# Patil_Sheet_1_20181208.net
KiCad netlist of a schematic drawn in Altium Designer
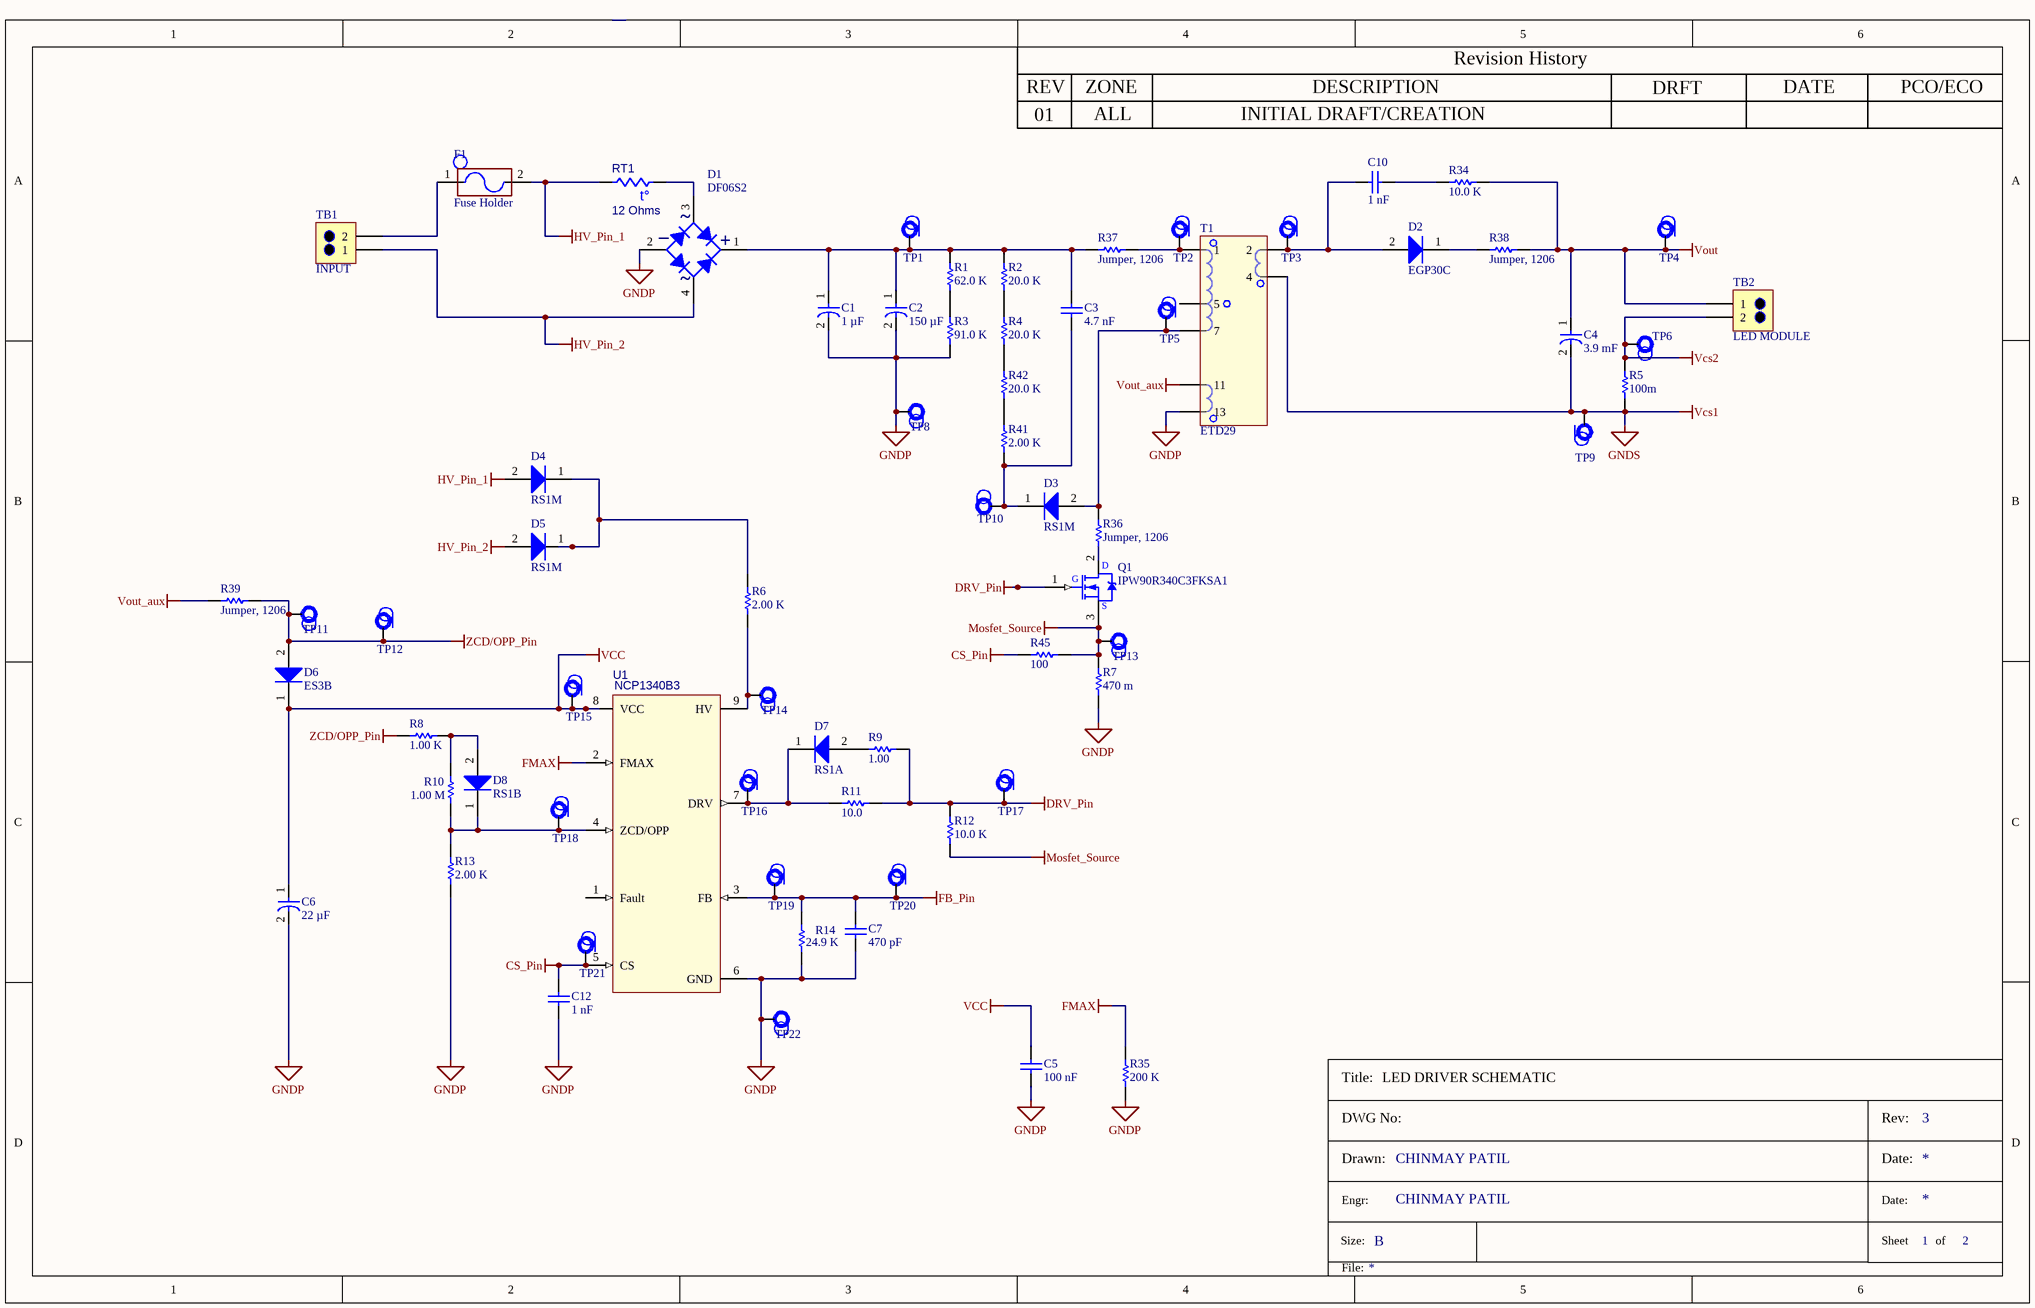
[diagram p0: Patil_Sheet_1_20181208.SchDoc]

(export (version "E")
  (design (tool "Eeschema 10.0.6"))
  (components
    (comp (ref "C1")
      (value "1 µF")
      (footprint "CAP-RAD-THRU-L17.5 X W7.8 X LS15.0 X H11.0MM")
      (description "Capacitor, Film, 1 µF, ±5%, 450 V, Metallized Polypropylene, Radial, Lead")
      (fields (field (name "DISTRIBUTOR PART NUMBER") "PCF1616-ND") (field (name "MANUFACTURER") "Panasonic"))
      (libsource (lib "CU_Boulder_ECEN5009_16-Capacitors") (part "16-0009-002"))
    )
    (comp (ref "C2")
      (value "150 µF")
      (footprint "CAP-SNAP_D25 X H35MM_A35")
      (description "Capacitor, Al. El., 150 µF, ±20%, 450 V, Radial, Snap")
      (fields
        (field (name "DISTRIBUTOR PART NUMBER") "493-17561-ND")
        (field (name "MANUFACTURER") "Nichicon")
      )
      (libsource (lib "CU_Boulder_ECEN5009_16-Capacitors") (part "16-0003-003"))
    )
    (comp (ref "C3")
      (value "4.7 nF")
      (footprint "CAP-1210M_IPC")
      (description "Capacitor, Ceramic, 4.7 nF, ±10%, 1000 V, X7R, 1210")
      (fields (field (name "TOLERANCE") "±10%") (field (name "MANUFACTURER") "Vishay Vitramon"))
      (libsource (lib "CU_Boulder_ECEN5009_16-Capacitors") (part "16-0010-003"))
    )
    (comp (ref "C4")
      (value "3.9 mF")
      (footprint "CAP-RAD-THRU-D18.0 X LS7.5 X H40.0MM")
      (description "Capacitor, Al. El., 3.9 mF, ±20%, 35 V, Radial, Lead")
      (fields (field (name "DISTRIBUTOR PART NUMBER") "493-1602-ND") (field (name "MANUFACTURER") "Nichicon"))
      (libsource (lib "CU_Boulder_ECEN5009_16-Capacitors") (part "16-0006-007"))
    )
    (comp (ref "C5")
      (value "100 nF")
      (footprint "CAP-0805M_IPC")
      (description "Capacitor, Ceramic, 100 nF, ±10%, 50 V, X7R, 0805")
      (fields (field (name "TOLERANCE") "±10%") (field (name "MANUFACTURER") "TDK"))
      (libsource (lib "CU_Boulder_ECEN5009_16-Capacitors") (part "16-0001-066"))
    )
    (comp (ref "C6")
      (value "22 µF")
      (footprint "CAPAE660X540M_CASE-D_IPC")
      (description "Capacitor, Al. El., 22 µF, ±20%, 35 V, SMT")
      (fields
        (field (name "DISTRIBUTOR PART NUMBER") "PCE4025CT-ND")
        (field (name "MANUFACTURER") "Panasonic")
      )
      (libsource (lib "CU_Boulder_ECEN5009_16-Capacitors") (part "16-0005-007"))
    )
    (comp (ref "C7")
      (value "470 pF")
      (footprint "CAP-0805M_IPC")
      (description "Capacitor, Ceramic, 470 pF, ±5%, 50 V, NP0, 0805")
      (fields (field (name "TOLERANCE") "±5%") (field (name "MANUFACTURER") "TDK"))
      (libsource (lib "CU_Boulder_ECEN5009_16-Capacitors") (part "16-0001-038"))
    )
    (comp (ref "C10")
      (value "1 nF")
      (footprint "CAP-1210M_IPC")
      (description "Capacitor, Ceramic, 1 nF, ±10%, 1000 V, X7R, 1210")
      (fields (field (name "TOLERANCE") "±10%") (field (name "MANUFACTURER") "Vishay Vitramon"))
      (libsource (lib "CU_Boulder_ECEN5009_16-Capacitors") (part "16-0010-001"))
    )
    (comp (ref "C12")
      (value "1 nF")
      (footprint "CAP-0805M_IPC")
      (description "Capacitor, Ceramic, 1 nF, ±5%, 50 V, NP0, 0805")
      (fields (field (name "TOLERANCE") "±5%") (field (name "MANUFACTURER") "TDK"))
      (libsource (lib "CU_Boulder_ECEN5009_16-Capacitors") (part "16-0001-042"))
    )
    (comp (ref "D1")
      (value "DF06S2")
      (footprint "SOIC510P1040X260-4M_IPC")
      (description "Diode, Bridge, Std Recovery, DF06S2, 600 V, 2 A, SDIP-4")
      (fields (field (name "DISTRIBUTOR PART NUMBER") "DF06S2CT-ND") (field (name "MANUFACTURER") "ON Semi"))
      (libsource (lib "CU_Boulder_ECEN5009_13-Diodes") (part "13-0015-001"))
    )
    (comp (ref "D2")
      (value "EGP30C")
      (footprint "DIO-AXIAL-DO-201AD")
      (description "Diode, Fast Recovery, EGP30C, 150 V, 3 A, DO-201AD")
      (fields (field (name "DISTRIBUTOR PART NUMBER") "EGP30CCT-ND") (field (name "MANUFACTURER") "ON Semi"))
      (libsource (lib "CU_Boulder_ECEN5009_13-Diodes") (part "13-0023-001"))
    )
    (comp (ref "D3")
      (value "RS1M")
      (footprint "DIODE-SMA-DO214AC")
      (description "Diode, Fast Recovery, RS1M, 1000 V, 1 A, SMA")
      (fields (field (name "DISTRIBUTOR PART NUMBER") "RS1MFSCT-ND") (field (name "MANUFACTURER") "ON Semi"))
      (libsource (lib "CU_Boulder_ECEN5009_13-Diodes") (part "13-0001-007"))
    )
    (comp (ref "D4")
      (value "RS1M")
      (footprint "DIODE-SMA-DO214AC")
      (description "Diode, Fast Recovery, RS1M, 1000 V, 1 A, SMA")
      (fields (field (name "DISTRIBUTOR PART NUMBER") "RS1MFSCT-ND") (field (name "MANUFACTURER") "ON Semi"))
      (libsource (lib "CU_Boulder_ECEN5009_13-Diodes") (part "13-0001-007"))
    )
    (comp (ref "D5")
      (value "RS1M")
      (footprint "DIODE-SMA-DO214AC")
      (description "Diode, Fast Recovery, RS1M, 1000 V, 1 A, SMA")
      (fields (field (name "DISTRIBUTOR PART NUMBER") "RS1MFSCT-ND") (field (name "MANUFACTURER") "ON Semi"))
      (libsource (lib "CU_Boulder_ECEN5009_13-Diodes") (part "13-0001-007"))
    )
    (comp (ref "D6")
      (value "ES3B")
      (footprint "DIODE-SMC-DO214AB")
      (description "Diode, Fast Recovery, ES3B, 100 V, 3 A, SMC")
      (fields
        (field (name "DISTRIBUTOR PART NUMBER") "ES3BFSCT-ND")
        (field (name "MANUFACTURER") "ON Semiconductor")
      )
      (libsource (lib "CU_Boulder_ECEN5009_13-Diodes") (part "13-0026-002"))
    )
    (comp (ref "D7")
      (value "RS1A")
      (footprint "DIODE-SMA-DO214AC")
      (description "Diode, Fast Recovery, RS1A, 50 V, 1 A, SMA")
      (fields (field (name "DISTRIBUTOR PART NUMBER") "RS1ACT-ND") (field (name "MANUFACTURER") "ON Semi"))
      (libsource (lib "CU_Boulder_ECEN5009_13-Diodes") (part "13-0001-001"))
    )
    (comp (ref "D8")
      (value "RS1B")
      (footprint "DIODE-SMA-DO214AC")
      (description "Diode, Fast Recovery, RS1B, 100 V, 1 A, SMA")
      (fields (field (name "DISTRIBUTOR PART NUMBER") "RS1BFSCT-ND") (field (name "MANUFACTURER") "ON Semi"))
      (libsource (lib "CU_Boulder_ECEN5009_13-Diodes") (part "13-0001-002"))
    )
    (comp (ref "F1")
      (value "Fuse Holder")
      (footprint "FUSE_HOLDER_3AG_4527")
      (description "Fuse Holder, TH, 5mm, 3AG")
      (fields
        (field (name "MANUFACTURER") "Keystone Electronics")
        (field (name "MANUFACTURER PART NUMBER") "4527")
      )
      (libsource (lib "CU_Boulder_ECEN5009_18-Electromechanical") (part "18-0012-001"))
    )
    (comp (ref "Q1")
      (value "IPW90R340C3FKSA1")
      (footprint "TO546P508X1588X2483-3A_IPC")
      (description "MOSFET, N-Channel, IPW90R340C3FKSA1, 900 V, 340 mOhm, TO-247")
      (fields
        (field (name "DISTRIBUTOR PART NUMBER") "IPW90R340C3FKSA1-ND")
        (field (name "MANUFACTURER") "Infineon")
      )
      (libsource (lib "CU_Boulder_ECEN5009_10-Transistors") (part "10-0016-002"))
    )
    (comp (ref "R1")
      (value "62.0 K")
      (footprint "RES-AXIAL-2W_IPC")
      (description "Resistor, TH, 62.0 K, 5%, 2 W, MO, Axial")
      (fields (field (name "DISTRIBUTOR PART NUMBER") "62KW-2-ND") (field (name "MANUFACTURER") "Yageo"))
      (libsource (lib "CU_Boulder_ECEN5009_15-Resistors") (part "15-0005-124"))
    )
    (comp (ref "R2")
      (value "20.0 K")
      (footprint "RES-2512M_IPC")
      (description "Resistor, SMT, 20.0 K, 5%, 1 W, 2512")
      (fields (field (name "DISTRIBUTOR PART NUMBER") "15-0004-129") (field (name "TOLERANCE") "5%"))
      (libsource (lib "CU_Boulder_ECEN5009_15-Resistors") (part "15-0004-129"))
    )
    (comp (ref "R3")
      (value "91.0 K")
      (footprint "RES-AXIAL-2W_IPC")
      (description "Resistor, TH, 91.0 K, 5%, 2 W, MO, Axial")
      (fields (field (name "DISTRIBUTOR PART NUMBER") "91KW-2-ND") (field (name "MANUFACTURER") "Yageo"))
      (libsource (lib "CU_Boulder_ECEN5009_15-Resistors") (part "15-0005-128"))
    )
    (comp (ref "R4")
      (value "20.0 K")
      (footprint "RES-2512M_IPC")
      (description "Resistor, SMT, 20.0 K, 5%, 1 W, 2512")
      (fields (field (name "DISTRIBUTOR PART NUMBER") "15-0004-129") (field (name "TOLERANCE") "5%"))
      (libsource (lib "CU_Boulder_ECEN5009_15-Resistors") (part "15-0004-129"))
    )
    (comp (ref "R5")
      (value "100m")
      (footprint "RES-2512M_IPC")
      (description "Resistor, SMT, 100m, 1%, 1 W, 2512")
      (fields (field (name "DISTRIBUTOR PART NUMBER") "311-0.1TCT-ND") (field (name "MANUFACTURER") "Yageo"))
      (libsource (lib "CU_Boulder_ECEN5009_15-Resistors") (part "15-0012-001"))
    )
    (comp (ref "R6")
      (value "2.00 K")
      (footprint "RES-AXIAL-2W_IPC")
      (description "Resistor, TH, 2.00 K, 5%, 2 W, MO, Axial")
      (fields (field (name "DISTRIBUTOR PART NUMBER") "2.0KW-2-ND") (field (name "MANUFACTURER") "Yageo"))
      (libsource (lib "CU_Boulder_ECEN5009_15-Resistors") (part "15-0005-088"))
    )
    (comp (ref "R7")
      (value "470 m")
      (footprint "RES-2512M_IPC")
      (description "Resistor, SMT, 470 m, 1%, 1 W, 2512")
      (fields (field (name "DISTRIBUTOR PART NUMBER") "311-0.47TCT-ND") (field (name "MANUFACTURER") "Yageo"))
      (libsource (lib "CU_Boulder_ECEN5009_15-Resistors") (part "15-0012-003"))
    )
    (comp (ref "R8")
      (value "1.00 K")
      (footprint "RES-2512M_IPC")
      (description "Resistor, SMT, 1.00 K, 5%, 1 W, 2512")
      (fields (field (name "DISTRIBUTOR PART NUMBER") "15-0004-098") (field (name "TOLERANCE") "5%"))
      (libsource (lib "CU_Boulder_ECEN5009_15-Resistors") (part "15-0004-098"))
    )
    (comp (ref "R9")
      (value "1.00")
      (footprint "RES-0805M_IPC")
      (description "Resistor, SMT, 1.00, 1%, 125 mW, 0805")
      (fields (field (name "TOLERANCE") "1%") (field (name "MANUFACTURER") "Yageo"))
      (libsource (lib "CU_Boulder_ECEN5009_15-Resistors") (part "15-0002-001"))
    )
    (comp (ref "R10")
      (value "1.00 M")
      (footprint "RES-1206M_IPC")
      (description "Resistor, SMT, 1.00 M, 1%, 250 mW, 1206")
      (fields (field (name "DISTRIBUTOR PART NUMBER") "15-0003-577") (field (name "MANUFACTURER") "Yageo"))
      (libsource (lib "CU_Boulder_ECEN5009_15-Resistors") (part "15-0003-577"))
    )
    (comp (ref "R11")
      (value "10.0")
      (footprint "RES-0805M_IPC")
      (description "Resistor, SMT, 10.0, 1%, 125 mW, 0805")
      (fields (field (name "DISTRIBUTOR PART NUMBER") "15-0002-097") (field (name "MANUFACTURER") "Yageo"))
      (libsource (lib "CU_Boulder_ECEN5009_15-Resistors") (part "15-0002-097"))
    )
    (comp (ref "R12")
      (value "10.0 K")
      (footprint "RES-1206M_IPC")
      (description "Resistor, SMT, 10.0 K, 1%, 250 mW, 1206")
      (fields (field (name "DISTRIBUTOR PART NUMBER") "15-0003-385") (field (name "MANUFACTURER") "Yageo"))
      (libsource (lib "CU_Boulder_ECEN5009_15-Resistors") (part "15-0003-385"))
    )
    (comp (ref "R13")
      (value "2.00 K")
      (footprint "RES-2512M_IPC")
      (description "Resistor, SMT, 2.00 K, 5%, 1 W, 2512")
      (fields (field (name "DISTRIBUTOR PART NUMBER") "15-0004-105") (field (name "TOLERANCE") "5%"))
      (libsource (lib "CU_Boulder_ECEN5009_15-Resistors") (part "15-0004-105"))
    )
    (comp (ref "R14")
      (value "24.9 K")
      (footprint "RES-1206M_IPC")
      (description "Resistor, SMT, 24.9 K, 1%, 250 mW, 1206")
      (fields (field (name "DISTRIBUTOR PART NUMBER") "15-0003-423") (field (name "MANUFACTURER") "Yageo"))
      (libsource (lib "CU_Boulder_ECEN5009_15-Resistors") (part "15-0003-423"))
    )
    (comp (ref "R34")
      (value "10.0 K")
      (footprint "RES-2512M_IPC")
      (description "Resistor, SMT, 10.0 K, 5%, 1 W, 2512")
      (fields (field (name "DISTRIBUTOR PART NUMBER") "15-0004-122") (field (name "TOLERANCE") "5%"))
      (libsource (lib "CU_Boulder_ECEN5009_15-Resistors") (part "15-0004-122"))
    )
    (comp (ref "R35")
      (value "200 K")
      (footprint "RES-1206M_IPC")
      (description "Resistor, SMT, 200 K, 1%, 250 mW, 1206")
      (fields (field (name "DISTRIBUTOR PART NUMBER") "15-0003-510") (field (name "MANUFACTURER") "Yageo"))
      (libsource (lib "CU_Boulder_ECEN5009_15-Resistors") (part "15-0003-510"))
    )
    (comp (ref "R36")
      (value "Jumper, 1206")
      (footprint "RES-1206M_IPC")
      (libsource (lib "CU_Boulder_ECEN5009_15-Resistors") (part "15-0001-002"))
    )
    (comp (ref "R37")
      (value "Jumper, 1206")
      (footprint "RES-1206M_IPC")
      (libsource (lib "CU_Boulder_ECEN5009_15-Resistors") (part "15-0001-002"))
    )
    (comp (ref "R38")
      (value "Jumper, 1206")
      (footprint "RES-1206M_IPC")
      (libsource (lib "CU_Boulder_ECEN5009_15-Resistors") (part "15-0001-002"))
    )
    (comp (ref "R39")
      (value "Jumper, 1206")
      (footprint "RES-1206M_IPC")
      (libsource (lib "CU_Boulder_ECEN5009_15-Resistors") (part "15-0001-002"))
    )
    (comp (ref "R41")
      (value "2.00 K")
      (footprint "RES-2512M_IPC")
      (description "Resistor, SMT, 2.00 K, 5%, 1 W, 2512")
      (fields (field (name "DISTRIBUTOR PART NUMBER") "15-0004-105") (field (name "TOLERANCE") "5%"))
      (libsource (lib "CU_Boulder_ECEN5009_15-Resistors") (part "15-0004-105"))
    )
    (comp (ref "R42")
      (value "20.0 K")
      (footprint "RES-2512M_IPC")
      (description "Resistor, SMT, 20.0 K, 5%, 1 W, 2512")
      (fields (field (name "DISTRIBUTOR PART NUMBER") "15-0004-129") (field (name "TOLERANCE") "5%"))
      (libsource (lib "CU_Boulder_ECEN5009_15-Resistors") (part "15-0004-129"))
    )
    (comp (ref "R45")
      (value "100")
      (footprint "RES-0805M_IPC")
      (description "Resistor, SMT, 100, 1%, 125 mW, 0805")
      (fields (field (name "DISTRIBUTOR PART NUMBER") "15-0002-193") (field (name "MANUFACTURER") "Yageo"))
      (libsource (lib "CU_Boulder_ECEN5009_15-Resistors") (part "15-0002-193"))
    )
    (comp (ref "RT1")
      (value "12 Ohms")
      (footprint "THERM-RADIAL-15.5MM_DIA_X6MM_THK")
      (description "Inrush Limiter, 12 Ohms, ±20%, 3 A, 15.5 mm, Radial")
      (fields (field (name "DISTRIBUTOR PART NUMBER") "317-1200-ND") (field (name "MANUFACTURER") "Cantherm"))
      (libsource (lib "CU_Boulder_ECEN5009_15-Resistors") (part "15-0010-003"))
    )
    (comp (ref "T1")
      (value "ETD29")
      (footprint "TRANS508P3530X3520X2500-13A_IPC")
      (description "Bobbin, ETD29, Horzontal, 13 Pins")
      (fields
        (field (name "DISTRIBUTOR PART NUMBER") "495-5455-ND")
        (field (name "MANUFACTURER") "TDK/EPCOS")
      )
      (libsource (lib "CU_Boulder_ECEN5009_17-Magnetics") (part "17-0002-002"))
    )
    (comp (ref "TB1")
      (value "INPUT")
      (footprint "CONN_2-POS_TERMINAL_BLOCK_1729128")
      (description "Terminal Block, 2 Pos., Vertical, 14-30 AWG, 5.08 mm")
      (fields
        (field (name "MANUFACTURER") "Phoenix Contact")
        (field (name "MANUFACTURER PART NUMBER") "1729128")
      )
      (libsource (lib "") (part "18-0008-001_1"))
    )
    (comp (ref "TB2")
      (value "LED MODULE")
      (footprint "CONN_2-POS_TERMINAL_BLOCK_1729128")
      (description "Terminal Block, 2 Pos., Vertical, 14-30 AWG, 5.08 mm")
      (fields
        (field (name "MANUFACTURER") "Phoenix Contact")
        (field (name "MANUFACTURER PART NUMBER") "1729128")
      )
      (libsource (lib "CU_Boulder_ECEN5009_18-Electromechanical") (part "18-0008-001"))
    )
    (comp (ref "TP1")
      (value "Test Point")
      (footprint "TP_SMT_LOOP-5019_3D")
      (description "Test Point, SMT, Miniature")
      (fields
        (field (name "MANUFACTURER") "Keystone Electronics")
        (field (name "MANUFACTURER PART NUMBER") "5019")
      )
      (libsource (lib "CU_Boulder_ECEN5009_18-Electromechanical") (part "18-0011-002"))
    )
    (comp (ref "TP2")
      (value "Test Point")
      (footprint "TP_SMT_LOOP-5019_3D")
      (description "Test Point, SMT, Miniature")
      (fields
        (field (name "MANUFACTURER") "Keystone Electronics")
        (field (name "MANUFACTURER PART NUMBER") "5019")
      )
      (libsource (lib "CU_Boulder_ECEN5009_18-Electromechanical") (part "18-0011-002"))
    )
    (comp (ref "TP3")
      (value "Test Point")
      (footprint "TP_SMT_LOOP-5019_3D")
      (description "Test Point, SMT, Miniature")
      (fields
        (field (name "MANUFACTURER") "Keystone Electronics")
        (field (name "MANUFACTURER PART NUMBER") "5019")
      )
      (libsource (lib "CU_Boulder_ECEN5009_18-Electromechanical") (part "18-0011-002"))
    )
    (comp (ref "TP4")
      (value "Test Point")
      (footprint "TP_SMT_LOOP-5019_3D")
      (description "Test Point, SMT, Miniature")
      (fields
        (field (name "MANUFACTURER") "Keystone Electronics")
        (field (name "MANUFACTURER PART NUMBER") "5019")
      )
      (libsource (lib "CU_Boulder_ECEN5009_18-Electromechanical") (part "18-0011-002"))
    )
    (comp (ref "TP5")
      (value "Test Point")
      (footprint "TP_SMT_LOOP-5019_3D")
      (description "Test Point, SMT, Miniature")
      (fields
        (field (name "MANUFACTURER") "Keystone Electronics")
        (field (name "MANUFACTURER PART NUMBER") "5019")
      )
      (libsource (lib "CU_Boulder_ECEN5009_18-Electromechanical") (part "18-0011-002"))
    )
    (comp (ref "TP6")
      (value "Test Point")
      (footprint "TP_SMT_LOOP-5019_3D")
      (description "Test Point, SMT, Miniature")
      (fields
        (field (name "MANUFACTURER") "Keystone Electronics")
        (field (name "MANUFACTURER PART NUMBER") "5019")
      )
      (libsource (lib "CU_Boulder_ECEN5009_18-Electromechanical") (part "18-0011-002"))
    )
    (comp (ref "TP8")
      (value "Test Point")
      (footprint "TP_SMT_LOOP-5019_3D")
      (description "Test Point, SMT, Miniature")
      (fields
        (field (name "MANUFACTURER") "Keystone Electronics")
        (field (name "MANUFACTURER PART NUMBER") "5019")
      )
      (libsource (lib "CU_Boulder_ECEN5009_18-Electromechanical") (part "18-0011-002"))
    )
    (comp (ref "TP9")
      (value "Test Point")
      (footprint "TP_SMT_LOOP-5019_3D")
      (description "Test Point, SMT, Miniature")
      (fields
        (field (name "MANUFACTURER") "Keystone Electronics")
        (field (name "MANUFACTURER PART NUMBER") "5019")
      )
      (libsource (lib "CU_Boulder_ECEN5009_18-Electromechanical") (part "18-0011-002"))
    )
    (comp (ref "TP10")
      (value "Test Point")
      (footprint "TP_SMT_LOOP-5019_3D")
      (description "Test Point, SMT, Miniature")
      (fields
        (field (name "MANUFACTURER") "Keystone Electronics")
        (field (name "MANUFACTURER PART NUMBER") "5019")
      )
      (libsource (lib "CU_Boulder_ECEN5009_18-Electromechanical") (part "18-0011-002"))
    )
    (comp (ref "TP11")
      (value "Test Point")
      (footprint "TP_SMT_LOOP-5019_3D")
      (description "Test Point, SMT, Miniature")
      (fields
        (field (name "MANUFACTURER") "Keystone Electronics")
        (field (name "MANUFACTURER PART NUMBER") "5019")
      )
      (libsource (lib "CU_Boulder_ECEN5009_18-Electromechanical") (part "18-0011-002"))
    )
    (comp (ref "TP12")
      (value "Test Point")
      (footprint "TP_SMT_LOOP-5019_3D")
      (description "Test Point, SMT, Miniature")
      (fields
        (field (name "MANUFACTURER") "Keystone Electronics")
        (field (name "MANUFACTURER PART NUMBER") "5019")
      )
      (libsource (lib "CU_Boulder_ECEN5009_18-Electromechanical") (part "18-0011-002"))
    )
    (comp (ref "TP13")
      (value "Test Point")
      (footprint "TP_SMT_LOOP-5019_3D")
      (description "Test Point, SMT, Miniature")
      (fields
        (field (name "MANUFACTURER") "Keystone Electronics")
        (field (name "MANUFACTURER PART NUMBER") "5019")
      )
      (libsource (lib "CU_Boulder_ECEN5009_18-Electromechanical") (part "18-0011-002"))
    )
    (comp (ref "TP14")
      (value "Test Point")
      (footprint "TP_SMT_LOOP-5019_3D")
      (description "Test Point, SMT, Miniature")
      (fields
        (field (name "MANUFACTURER") "Keystone Electronics")
        (field (name "MANUFACTURER PART NUMBER") "5019")
      )
      (libsource (lib "CU_Boulder_ECEN5009_18-Electromechanical") (part "18-0011-002"))
    )
    (comp (ref "TP15")
      (value "Test Point")
      (footprint "TP_SMT_LOOP-5019_3D")
      (description "Test Point, SMT, Miniature")
      (fields
        (field (name "MANUFACTURER") "Keystone Electronics")
        (field (name "MANUFACTURER PART NUMBER") "5019")
      )
      (libsource (lib "CU_Boulder_ECEN5009_18-Electromechanical") (part "18-0011-002"))
    )
    (comp (ref "TP16")
      (value "Test Point")
      (footprint "TP_SMT_LOOP-5019_3D")
      (description "Test Point, SMT, Miniature")
      (fields
        (field (name "MANUFACTURER") "Keystone Electronics")
        (field (name "MANUFACTURER PART NUMBER") "5019")
      )
      (libsource (lib "CU_Boulder_ECEN5009_18-Electromechanical") (part "18-0011-002"))
    )
    (comp (ref "TP17")
      (value "Test Point")
      (footprint "TP_SMT_LOOP-5019_3D")
      (description "Test Point, SMT, Miniature")
      (fields
        (field (name "MANUFACTURER") "Keystone Electronics")
        (field (name "MANUFACTURER PART NUMBER") "5019")
      )
      (libsource (lib "CU_Boulder_ECEN5009_18-Electromechanical") (part "18-0011-002"))
    )
    (comp (ref "TP18")
      (value "Test Point")
      (footprint "TP_SMT_LOOP-5019_3D")
      (description "Test Point, SMT, Miniature")
      (fields
        (field (name "MANUFACTURER") "Keystone Electronics")
        (field (name "MANUFACTURER PART NUMBER") "5019")
      )
      (libsource (lib "CU_Boulder_ECEN5009_18-Electromechanical") (part "18-0011-002"))
    )
    (comp (ref "TP19")
      (value "Test Point")
      (footprint "TP_SMT_LOOP-5019_3D")
      (description "Test Point, SMT, Miniature")
      (fields
        (field (name "MANUFACTURER") "Keystone Electronics")
        (field (name "MANUFACTURER PART NUMBER") "5019")
      )
      (libsource (lib "CU_Boulder_ECEN5009_18-Electromechanical") (part "18-0011-002"))
    )
    (comp (ref "TP20")
      (value "Test Point")
      (footprint "TP_SMT_LOOP-5019_3D")
      (description "Test Point, SMT, Miniature")
      (fields
        (field (name "MANUFACTURER") "Keystone Electronics")
        (field (name "MANUFACTURER PART NUMBER") "5019")
      )
      (libsource (lib "CU_Boulder_ECEN5009_18-Electromechanical") (part "18-0011-002"))
    )
    (comp (ref "TP21")
      (value "Test Point")
      (footprint "TP_SMT_LOOP-5019_3D")
      (description "Test Point, SMT, Miniature")
      (fields
        (field (name "MANUFACTURER") "Keystone Electronics")
        (field (name "MANUFACTURER PART NUMBER") "5019")
      )
      (libsource (lib "CU_Boulder_ECEN5009_18-Electromechanical") (part "18-0011-002"))
    )
    (comp (ref "TP22")
      (value "Test Point")
      (footprint "TP_SMT_LOOP-5019_3D")
      (description "Test Point, SMT, Miniature")
      (fields
        (field (name "MANUFACTURER") "Keystone Electronics")
        (field (name "MANUFACTURER PART NUMBER") "5019")
      )
      (libsource (lib "CU_Boulder_ECEN5009_18-Electromechanical") (part "18-0011-002"))
    )
    (comp (ref "U1")
      (value "NCP1340B3")
      (footprint "SOIC100P600X175-9M")
      (description "Controller, PWM, NCP1340B3, SOIC-9")
      (fields
        (field (name "DISTRIBUTOR PART NUMBER") "NCP1340B3D1R2GOSCT-ND")
        (field (name "MANUFACTURER") "On Semi")
      )
      (libsource (lib "CU_Boulder_ECEN5009_11-Chinmay_ICs,Analog") (part "11-0021-001"))
    )
  )
  (nets
    (net (code "1") (name "CS_Pin") (class "Default")
      (node (ref "C12") (pin "2") (pinfunction "2_2") (pintype "passive"))
      (node (ref "R45") (pin "1") (pinfunction "1_1") (pintype "passive"))
      (node (ref "TP21") (pin "1") (pinfunction "GND_TP_1") (pintype "passive"))
      (node (ref "U1") (pin "5") (pinfunction "CS_5") (pintype "input"))
    )
    (net (code "2") (name "DRV_Pin") (class "Default")
      (node (ref "Q1") (pin "1") (pinfunction "GATE_1") (pintype "input"))
      (node (ref "R11") (pin "2") (pinfunction "2_2") (pintype "passive"))
      (node (ref "R12") (pin "2") (pinfunction "2_2") (pintype "passive"))
      (node (ref "R9") (pin "2") (pinfunction "2_2") (pintype "passive"))
      (node (ref "TP17") (pin "1") (pinfunction "GND_TP_1") (pintype "passive"))
    )
    (net (code "3") (name "FB_Pin") (class "Default")
      (node (ref "C7") (pin "2") (pinfunction "2_2") (pintype "passive"))
      (node (ref "R14") (pin "2") (pinfunction "2_2") (pintype "passive"))
      (node (ref "TP19") (pin "1") (pinfunction "GND_TP_1") (pintype "passive"))
      (node (ref "TP20") (pin "1") (pinfunction "GND_TP_1") (pintype "passive"))
      (node (ref "U1") (pin "3") (pinfunction "FB_3") (pintype "input"))
    )
    (net (code "4") (name "FMAX") (class "Default")
      (node (ref "R35") (pin "2") (pinfunction "2_2") (pintype "passive"))
      (node (ref "U1") (pin "2") (pinfunction "FMAX_2") (pintype "input"))
    )
    (net (code "5") (name "GNDP") (class "Default")
      (node (ref "C1") (pin "2") (pinfunction "Cathode_2") (pintype "passive"))
      (node (ref "C12") (pin "1") (pinfunction "1_1") (pintype "passive"))
      (node (ref "C2") (pin "2") (pinfunction "Cathode_2") (pintype "passive"))
      (node (ref "C5") (pin "1") (pinfunction "1_1") (pintype "passive"))
      (node (ref "C6") (pin "2") (pinfunction "Cathode_2") (pintype "passive"))
      (node (ref "C7") (pin "1") (pinfunction "1_1") (pintype "passive"))
      (node (ref "D1") (pin "2") (pinfunction "A_2") (pintype "passive"))
      (node (ref "R13") (pin "1") (pinfunction "1_1") (pintype "passive"))
      (node (ref "R14") (pin "1") (pinfunction "1_1") (pintype "passive"))
      (node (ref "R3") (pin "1") (pinfunction "1_1") (pintype "passive"))
      (node (ref "R35") (pin "1") (pinfunction "1_1") (pintype "passive"))
      (node (ref "R7") (pin "1") (pinfunction "1_1") (pintype "passive"))
      (node (ref "T1") (pin "13") (pinfunction "13_13") (pintype "power_in"))
      (node (ref "TP22") (pin "1") (pinfunction "GND_TP_1") (pintype "passive"))
      (node (ref "TP8") (pin "1") (pinfunction "GND_TP_1") (pintype "passive"))
      (node (ref "U1") (pin "6") (pinfunction "GND_6") (pintype "power_in"))
    )
    (net (code "6") (name "GNDS") (class "Default")
      (node (ref "C4") (pin "2") (pinfunction "Cathode_2") (pintype "passive"))
      (node (ref "R5") (pin "1") (pinfunction "1_1") (pintype "passive"))
      (node (ref "T1") (pin "4") (pinfunction "4_4") (pintype "power_in"))
      (node (ref "TP9") (pin "1") (pinfunction "GND_TP_1") (pintype "passive"))
    )
    (net (code "7") (name "HV_Pin_1") (class "Default")
      (node (ref "D4") (pin "2") (pinfunction "K_2") (pintype "passive"))
      (node (ref "F1") (pin "2") (pinfunction "2_2") (pintype "passive"))
      (node (ref "RT1") (pin "2") (pinfunction "2_2") (pintype "passive"))
    )
    (net (code "8") (name "HV_Pin_2") (class "Default")
      (node (ref "D1") (pin "4") (pinfunction "C_4") (pintype "passive"))
      (node (ref "D5") (pin "2") (pinfunction "K_2") (pintype "passive"))
      (node (ref "TB1") (pin "1") (pinfunction "1_1") (pintype "passive"))
    )
    (net (code "9") (name "Mosfet_Source") (class "Default")
      (node (ref "Q1") (pin "3") (pinfunction "SOURCE_3") (pintype "passive"))
      (node (ref "R12") (pin "1") (pinfunction "1_1") (pintype "passive"))
      (node (ref "R45") (pin "2") (pinfunction "2_2") (pintype "passive"))
      (node (ref "R7") (pin "2") (pinfunction "2_2") (pintype "passive"))
      (node (ref "TP13") (pin "1") (pinfunction "GND_TP_1") (pintype "passive"))
    )
    (net (code "10") (name "Net-(C1-Anode)") (class "Default")
      (node (ref "C1") (pin "1") (pinfunction "Anode_1") (pintype "passive"))
      (node (ref "C2") (pin "1") (pinfunction "Anode_1") (pintype "passive"))
      (node (ref "C3") (pin "2") (pinfunction "2_2") (pintype "passive"))
      (node (ref "D1") (pin "1") (pinfunction "K_1") (pintype "passive"))
      (node (ref "R1") (pin "2") (pinfunction "2_2") (pintype "passive"))
      (node (ref "R2") (pin "2") (pinfunction "2_2") (pintype "passive"))
      (node (ref "R37") (pin "2") (pinfunction "2_2") (pintype "passive"))
      (node (ref "TP1") (pin "1") (pinfunction "GND_TP_1") (pintype "passive"))
    )
    (net (code "11") (name "Net-(C10-Pad2)") (class "Default")
      (node (ref "C10") (pin "2") (pinfunction "2_2") (pintype "passive"))
      (node (ref "R34") (pin "1") (pinfunction "1_1") (pintype "passive"))
    )
    (net (code "12") (name "Net-(D1-C-Pad3)") (class "Default")
      (node (ref "D1") (pin "3") (pinfunction "C_3") (pintype "passive"))
      (node (ref "RT1") (pin "1") (pinfunction "1_1") (pintype "passive"))
    )
    (net (code "13") (name "Net-(D2-A)") (class "Default")
      (node (ref "D2") (pin "1") (pinfunction "A_1") (pintype "passive"))
      (node (ref "R38") (pin "2") (pinfunction "2_2") (pintype "passive"))
    )
    (net (code "14") (name "Net-(D2-K)") (class "Default")
      (node (ref "C10") (pin "1") (pinfunction "1_1") (pintype "passive"))
      (node (ref "D2") (pin "2") (pinfunction "K_2") (pintype "passive"))
      (node (ref "T1") (pin "2") (pinfunction "2_2") (pintype "power_in"))
      (node (ref "TP3") (pin "1") (pinfunction "GND_TP_1") (pintype "passive"))
    )
    (net (code "15") (name "Net-(D3-A)") (class "Default")
      (node (ref "C3") (pin "1") (pinfunction "1_1") (pintype "passive"))
      (node (ref "D3") (pin "1") (pinfunction "A_1") (pintype "passive"))
      (node (ref "R41") (pin "1") (pinfunction "1_1") (pintype "passive"))
      (node (ref "TP10") (pin "1") (pinfunction "GND_TP_1") (pintype "passive"))
    )
    (net (code "16") (name "Net-(D3-K)") (class "Default")
      (node (ref "D3") (pin "2") (pinfunction "K_2") (pintype "passive"))
      (node (ref "R36") (pin "2") (pinfunction "2_2") (pintype "passive"))
      (node (ref "T1") (pin "7") (pinfunction "7_7") (pintype "power_in"))
      (node (ref "TP5") (pin "1") (pinfunction "GND_TP_1") (pintype "passive"))
    )
    (net (code "17") (name "Net-(D4-A)") (class "Default")
      (node (ref "D4") (pin "1") (pinfunction "A_1") (pintype "passive"))
      (node (ref "D5") (pin "1") (pinfunction "A_1") (pintype "passive"))
      (node (ref "R6") (pin "2") (pinfunction "2_2") (pintype "passive"))
    )
    (net (code "18") (name "Net-(D7-A)") (class "Default")
      (node (ref "D7") (pin "1") (pinfunction "A_1") (pintype "passive"))
      (node (ref "R11") (pin "1") (pinfunction "1_1") (pintype "passive"))
      (node (ref "TP16") (pin "1") (pinfunction "GND_TP_1") (pintype "passive"))
      (node (ref "U1") (pin "7") (pinfunction "DRV_7") (pintype "output"))
    )
    (net (code "19") (name "Net-(D7-K)") (class "Default")
      (node (ref "D7") (pin "2") (pinfunction "K_2") (pintype "passive"))
      (node (ref "R9") (pin "1") (pinfunction "1_1") (pintype "passive"))
    )
    (net (code "20") (name "Net-(D8-A)") (class "Default")
      (node (ref "D8") (pin "1") (pinfunction "A_1") (pintype "passive"))
      (node (ref "R10") (pin "2") (pinfunction "2_2") (pintype "passive"))
      (node (ref "R13") (pin "2") (pinfunction "2_2") (pintype "passive"))
      (node (ref "TP18") (pin "1") (pinfunction "GND_TP_1") (pintype "passive"))
      (node (ref "U1") (pin "4") (pinfunction "ZCD/OPP_4") (pintype "input"))
    )
    (net (code "21") (name "Net-(D8-K)") (class "Default")
      (node (ref "D8") (pin "2") (pinfunction "K_2") (pintype "passive"))
      (node (ref "R10") (pin "1") (pinfunction "1_1") (pintype "passive"))
      (node (ref "R8") (pin "2") (pinfunction "2_2") (pintype "passive"))
    )
    (net (code "22") (name "Net-(F1-Pad1)") (class "Default")
      (node (ref "F1") (pin "1") (pinfunction "1_1") (pintype "passive"))
      (node (ref "TB1") (pin "2") (pinfunction "2_2") (pintype "passive"))
    )
    (net (code "23") (name "Net-(Q1-DRAIN)") (class "Default")
      (node (ref "Q1") (pin "2") (pinfunction "DRAIN_2") (pintype "passive"))
      (node (ref "R36") (pin "1") (pinfunction "1_1") (pintype "passive"))
    )
    (net (code "24") (name "Net-(R1-Pad1)") (class "Default")
      (node (ref "R1") (pin "1") (pinfunction "1_1") (pintype "passive"))
      (node (ref "R3") (pin "2") (pinfunction "2_2") (pintype "passive"))
    )
    (net (code "25") (name "Net-(R2-Pad1)") (class "Default")
      (node (ref "R2") (pin "1") (pinfunction "1_1") (pintype "passive"))
      (node (ref "R4") (pin "2") (pinfunction "2_2") (pintype "passive"))
    )
    (net (code "26") (name "Net-(R4-Pad1)") (class "Default")
      (node (ref "R4") (pin "1") (pinfunction "1_1") (pintype "passive"))
      (node (ref "R42") (pin "2") (pinfunction "2_2") (pintype "passive"))
    )
    (net (code "27") (name "Net-(R41-Pad2)") (class "Default")
      (node (ref "R41") (pin "2") (pinfunction "2_2") (pintype "passive"))
      (node (ref "R42") (pin "1") (pinfunction "1_1") (pintype "passive"))
    )
    (net (code "28") (name "Net-(TP2-GND_TP)") (class "Default")
      (node (ref "R37") (pin "1") (pinfunction "1_1") (pintype "passive"))
      (node (ref "T1") (pin "1") (pinfunction "1_1") (pintype "power_in"))
      (node (ref "TP2") (pin "1") (pinfunction "GND_TP_1") (pintype "passive"))
    )
    (net (code "29") (name "Net-(TP14-GND_TP)") (class "Default")
      (node (ref "R6") (pin "1") (pinfunction "1_1") (pintype "passive"))
      (node (ref "TP14") (pin "1") (pinfunction "GND_TP_1") (pintype "passive"))
      (node (ref "U1") (pin "9") (pinfunction "HV_9") (pintype "power_in"))
    )
    (net (code "30") (name "VCC") (class "Default")
      (node (ref "C5") (pin "2") (pinfunction "2_2") (pintype "passive"))
      (node (ref "C6") (pin "1") (pinfunction "Anode_1") (pintype "passive"))
      (node (ref "D6") (pin "1") (pinfunction "A_1") (pintype "passive"))
      (node (ref "TP15") (pin "1") (pinfunction "GND_TP_1") (pintype "passive"))
      (node (ref "U1") (pin "8") (pinfunction "VCC_8") (pintype "power_in"))
    )
    (net (code "31") (name "Vcs2") (class "Default")
      (node (ref "R5") (pin "2") (pinfunction "2_2") (pintype "passive"))
      (node (ref "TB2") (pin "2") (pinfunction "2_2") (pintype "passive"))
      (node (ref "TP6") (pin "1") (pinfunction "GND_TP_1") (pintype "passive"))
    )
    (net (code "32") (name "Vout") (class "Default")
      (node (ref "C4") (pin "1") (pinfunction "Anode_1") (pintype "passive"))
      (node (ref "R34") (pin "2") (pinfunction "2_2") (pintype "passive"))
      (node (ref "R38") (pin "1") (pinfunction "1_1") (pintype "passive"))
      (node (ref "TB2") (pin "1") (pinfunction "1_1") (pintype "passive"))
      (node (ref "TP4") (pin "1") (pinfunction "GND_TP_1") (pintype "passive"))
    )
    (net (code "33") (name "Vout_aux") (class "Default")
      (node (ref "R39") (pin "2") (pinfunction "2_2") (pintype "passive"))
      (node (ref "T1") (pin "11") (pinfunction "11_11") (pintype "power_in"))
    )
    (net (code "34") (name "ZCD{slash}OPP_Pin") (class "Default")
      (node (ref "D6") (pin "2") (pinfunction "K_2") (pintype "passive"))
      (node (ref "R39") (pin "1") (pinfunction "1_1") (pintype "passive"))
      (node (ref "R8") (pin "1") (pinfunction "1_1") (pintype "passive"))
      (node (ref "TP11") (pin "1") (pinfunction "GND_TP_1") (pintype "passive"))
      (node (ref "TP12") (pin "1") (pinfunction "GND_TP_1") (pintype "passive"))
    )
    (net (code "35") (name "unconnected-(T1-Pad5)") (class "Default")
      (node (ref "T1") (pin "5") (pinfunction "5_5") (pintype "power_in"))
    )
    (net (code "36") (name "unconnected-(U1-Fault-Pad1)") (class "Default")
      (node (ref "U1") (pin "1") (pinfunction "Fault_1") (pintype "input"))
    )
  )
)
